# sensor_v21.net
KiCad netlist of a schematic drawn in EAGLE
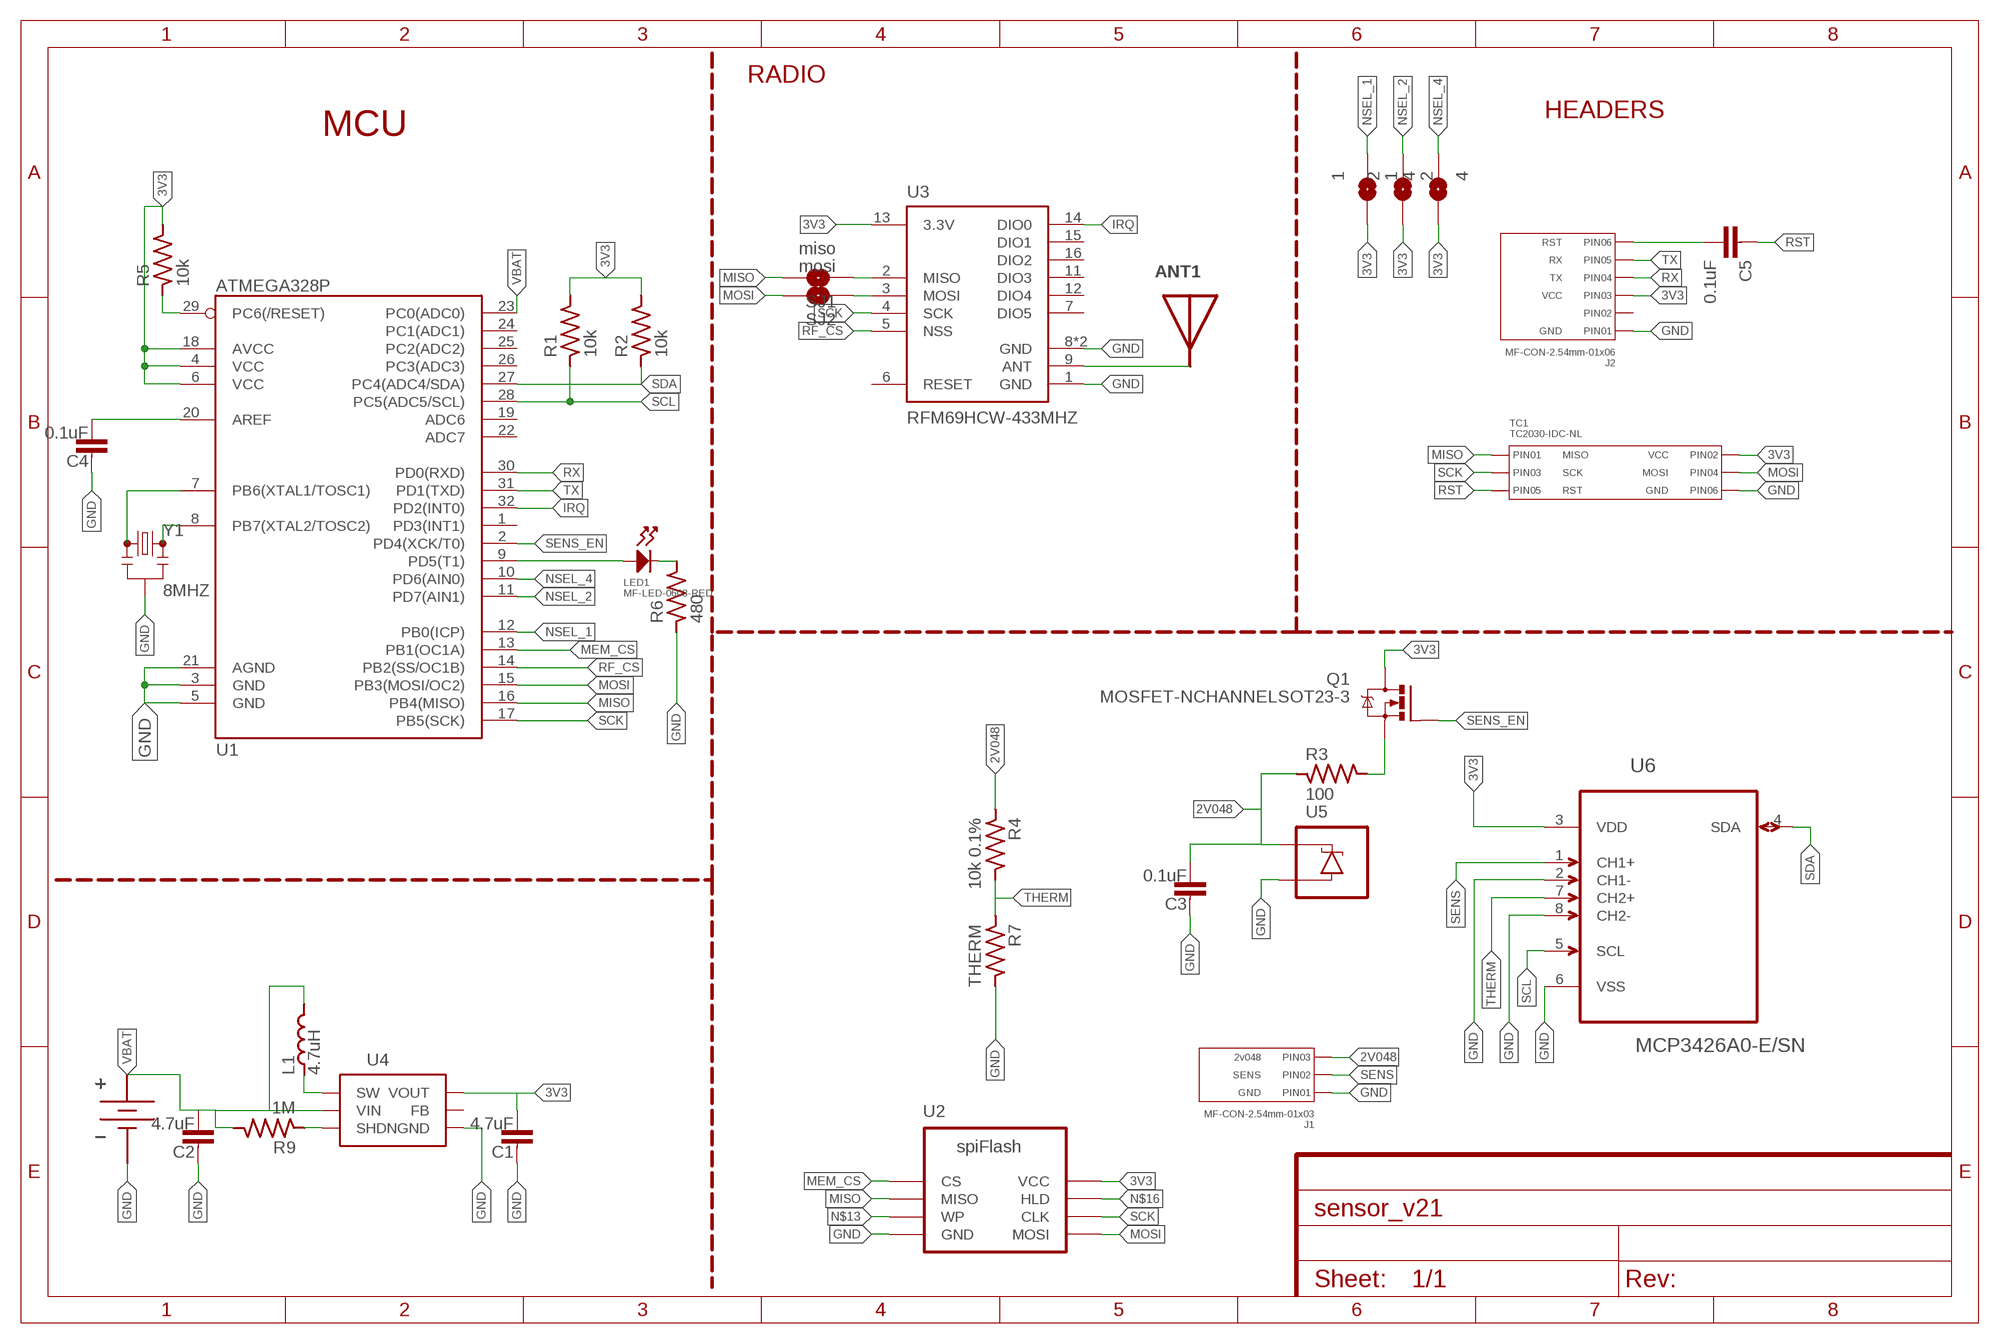
[diagram p0: schematic, sheet 1]

(export (version "E")
  (design (tool "Eeschema 10.0.6"))
  (components
    (comp (ref "1")
      (value "1")
      (footprint "eagle-import:SJ_2S-NOTRACE")
      (libsource (lib "eagle-import") (part "SOLDERJUMPERNC2"))
    )
    (comp (ref "2")
      (value "2")
      (footprint "eagle-import:SJ_2S-NOTRACE")
      (libsource (lib "eagle-import") (part "SOLDERJUMPERNC2"))
    )
    (comp (ref "4")
      (value "4")
      (footprint "eagle-import:SJ_2S-NOTRACE")
      (libsource (lib "eagle-import") (part "SOLDERJUMPERNC2"))
    )
    (comp (ref "ANT1")
      (value "ANTENNA-433_CHIP")
      (footprint "eagle-import:ANT_433_CHIP")
      (fields (field (name "PARTNO") "0433AT62A0020E"))
      (libsource (lib "eagle-import") (part "ANTENNA-433_CHIP"))
    )
    (comp (ref "C1")
      (value "4.7uF")
      (footprint "eagle-import:C0603-N")
      (libsource (lib "eagle-import") (part "CAPACITOR_NP0603-N"))
    )
    (comp (ref "C2")
      (value "4.7uF")
      (footprint "eagle-import:C0603-N")
      (libsource (lib "eagle-import") (part "CAPACITOR_NP0603-N"))
    )
    (comp (ref "C3")
      (value "0.1uF")
      (footprint "eagle-import:C0603-N")
      (libsource (lib "eagle-import") (part "CAPACITOR_NP0603-N"))
    )
    (comp (ref "C4")
      (value "0.1uF")
      (footprint "eagle-import:C0603-N")
      (libsource (lib "eagle-import") (part "CAPACITOR_NP0603-N"))
    )
    (comp (ref "C5")
      (value "0.1uF")
      (footprint "eagle-import:C0603-N")
      (libsource (lib "eagle-import") (part "CAPACITOR0603-N"))
    )
    (comp (ref "J1")
      (value "MF-CON-2.54mm-01x03")
      (footprint "eagle-import:PTH_2.54MM_01X03")
      (fields
        (field (name "HOUSEPART") "YES")
        (field (name "LABEL01") "GND")
        (field (name "LABEL02") "SENS")
        (field (name "LABEL03") "2v048")
        (field (name "PARTNO") "0022053031")
      )
      (libsource (lib "eagle-import") (part "CON_01X03_PTH_2.54MM"))
    )
    (comp (ref "J2")
      (value "MF-CON-2.54mm-01x06")
      (footprint "eagle-import:PTH_2.54MM_01X06")
      (fields
        (field (name "HOUSEPART") "YES")
        (field (name "LABEL01") "GND")
        (field (name "LABEL03") "VCC")
        (field (name "LABEL04") "TX")
        (field (name "LABEL05") "RX")
        (field (name "LABEL06") "RST")
      )
      (libsource (lib "eagle-import") (part "CON_01X06_PTH_2.54MM"))
    )
    (comp (ref "L1")
      (value "4.7uH")
      (footprint "eagle-import:L3030")
      (libsource (lib "eagle-import") (part "INDUCTOR3030"))
    )
    (comp (ref "LED1")
      (value "MF-LED-0603-RED")
      (footprint "eagle-import:LED0603")
      (fields (field (name "HOUSEPART") "YES"))
      (libsource (lib "eagle-import") (part "LED_SINGLE-0603-RED"))
    )
    (comp (ref "Q1")
      (value "MOSFET-NCHANNELSOT23-3")
      (footprint "eagle-import:SOT23-3")
      (libsource (lib "eagle-import") (part "MOSFET-NCHANNELSOT23-3"))
    )
    (comp (ref "R1")
      (value "10k")
      (footprint "eagle-import:R0603-N")
      (libsource (lib "eagle-import") (part "RESISTOR0603-N"))
    )
    (comp (ref "R2")
      (value "10k")
      (footprint "eagle-import:R0603-N")
      (libsource (lib "eagle-import") (part "RESISTOR0603-N"))
    )
    (comp (ref "R3")
      (value "100")
      (footprint "eagle-import:R0603-N")
      (libsource (lib "eagle-import") (part "RESISTOR0603-N"))
    )
    (comp (ref "R4")
      (value "10k 0.1%")
      (footprint "eagle-import:R0603-N")
      (fields (field (name "PARTNO") "0.1% !!"))
      (libsource (lib "eagle-import") (part "RESISTOR0603-N"))
    )
    (comp (ref "R5")
      (value "10k")
      (footprint "eagle-import:R0603-N")
      (libsource (lib "eagle-import") (part "RESISTOR0603-N"))
    )
    (comp (ref "R6")
      (value "480")
      (footprint "eagle-import:R0603-N")
      (libsource (lib "eagle-import") (part "RESISTOR0603-N"))
    )
    (comp (ref "R7")
      (value "THERM")
      (footprint "eagle-import:R0603-N")
      (fields (field (name "PARTNO") "FIND PART!!"))
      (libsource (lib "eagle-import") (part "RESISTOR0603-N"))
    )
    (comp (ref "R9")
      (value "1M")
      (footprint "eagle-import:R0603-N")
      (libsource (lib "eagle-import") (part "RESISTOR0603-N"))
    )
    (comp (ref "SJ1")
      (value "miso")
      (footprint "eagle-import:SJ_2S-NOTRACE")
      (libsource (lib "eagle-import") (part "SOLDERJUMPERNC2"))
    )
    (comp (ref "SJ2")
      (value "mosi")
      (footprint "eagle-import:SJ_2S-NOTRACE")
      (libsource (lib "eagle-import") (part "SOLDERJUMPERNC2"))
    )
    (comp (ref "TC1")
      (value "TC2030-IDC-NL")
      (footprint "eagle-import:TC2030-IDC-NL")
      (fields (field (name "HOUSEPART") "NO") (field (name "PARTNO") "NA"))
      (libsource (lib "eagle-import") (part "CON_02X03_TC2030-IDC-NL_AVRISP"))
    )
    (comp (ref "U$1")
      (value "KEYSTONEAAHOLDER_2CELL")
      (footprint "eagle-import:KEYSTONEAAHOLDER_2CELL")
      (libsource (lib "eagle-import") (part "KEYSTONEAAHOLDER_2CELL"))
    )
    (comp (ref "U1")
      (value "ATMEGA328P")
      (footprint "eagle-import:TQFP32")
      (libsource (lib "eagle-import") (part "ATMEGA328P_SMD-AU"))
    )
    (comp (ref "U2")
      (value "WINBOND_FLASH_4MBIT-SOIC")
      (footprint "eagle-import:SOIC8")
      (libsource (lib "eagle-import") (part "WINBOND_FLASH_4MBIT-SOIC"))
    )
    (comp (ref "U3")
      (value "RFM69HCW-433MHZ")
      (footprint "eagle-import:RFM69HCW-XXXS2")
      (fields (field (name "PARTNO") "COM-13910"))
      (libsource (lib "eagle-import") (part "RFM69HCW-433MHZ"))
    )
    (comp (ref "U4")
      (value "AAT1217-SOT23-6")
      (footprint "eagle-import:SOT23-6")
      (fields (field (name "PARTNO") "AAT1217ICA-3.3-T1"))
      (libsource (lib "eagle-import") (part "AAT1217-SOT23-6"))
    )
    (comp (ref "U5")
      (value "LM4040-SOT-23-3")
      (footprint "eagle-import:SOT23-3")
      (fields (field (name "PARTNO") "LM4040AIM3-2.0/NOPB "))
      (libsource (lib "eagle-import") (part "LM4040-SOT-23-3"))
    )
    (comp (ref "U6")
      (value "MCP3426A0-E/SN")
      (footprint "eagle-import:SOIC127P600X175-8N")
      (libsource (lib "eagle-import") (part "MCP3426A0-E/SN"))
    )
    (comp (ref "Y1")
      (value "8MHZ")
      (footprint "eagle-import:RESONATOR-SMD")
      (fields (field (name "PARTNO") "CSTCE8M00G55-R0"))
      (libsource (lib "eagle-import") (part "RESONATOR8MHZ"))
    )
  )
  (nets
    (net (code "1") (name "2V048") (class "Default")
      (node (ref "C3") (pin "2") (pinfunction "2_2") (pintype "passive"))
      (node (ref "J1") (pin "P$3") (pinfunction "PIN3_P$3") (pintype "bidirectional"))
      (node (ref "R3") (pin "1") (pinfunction "P$1_1") (pintype "passive"))
      (node (ref "R4") (pin "1") (pinfunction "P$1_1") (pintype "passive"))
      (node (ref "U5") (pin "1") (pinfunction "C_1") (pintype "bidirectional"))
    )
    (net (code "2") (name "3V3") (class "Default")
      (node (ref "1") (pin "2") (pinfunction "2_2") (pintype "passive"))
      (node (ref "2") (pin "2") (pinfunction "2_2") (pintype "passive"))
      (node (ref "4") (pin "2") (pinfunction "2_2") (pintype "passive"))
      (node (ref "C1") (pin "2") (pinfunction "2_2") (pintype "passive"))
      (node (ref "J2") (pin "P$3") (pinfunction "PIN3_P$3") (pintype "bidirectional"))
      (node (ref "Q1") (pin "3") (pinfunction "D_3") (pintype "passive"))
      (node (ref "R1") (pin "2") (pinfunction "P$2_2") (pintype "passive"))
      (node (ref "R2") (pin "2") (pinfunction "P$2_2") (pintype "passive"))
      (node (ref "R5") (pin "2") (pinfunction "P$2_2") (pintype "passive"))
      (node (ref "TC1") (pin "P$2") (pinfunction "PIN2_P$2") (pintype "bidirectional"))
      (node (ref "U1") (pin "18") (pinfunction "AVCC_18") (pintype "bidirectional"))
      (node (ref "U1") (pin "4") (pinfunction "VCC_4") (pintype "bidirectional"))
      (node (ref "U1") (pin "6") (pinfunction "VCC_6") (pintype "bidirectional"))
      (node (ref "U2") (pin "8") (pinfunction "VCC_8") (pintype "bidirectional"))
      (node (ref "U3") (pin "13") (pinfunction "3.3V_13") (pintype "power_in"))
      (node (ref "U4") (pin "5") (pinfunction "VOUT_5") (pintype "bidirectional"))
      (node (ref "U6") (pin "3") (pinfunction "VDD_3") (pintype "power_in"))
    )
    (net (code "3") (name "GND") (class "Default")
      (node (ref "C1") (pin "1") (pinfunction "1_1") (pintype "passive"))
      (node (ref "C2") (pin "1") (pinfunction "1_1") (pintype "passive"))
      (node (ref "C3") (pin "1") (pinfunction "1_1") (pintype "passive"))
      (node (ref "C4") (pin "1") (pinfunction "1_1") (pintype "passive"))
      (node (ref "J1") (pin "P$1") (pinfunction "PIN1_P$1") (pintype "bidirectional"))
      (node (ref "J2") (pin "P$1") (pinfunction "PIN1_P$1") (pintype "bidirectional"))
      (node (ref "R6") (pin "1") (pinfunction "P$1_1") (pintype "passive"))
      (node (ref "R7") (pin "2") (pinfunction "P$2_2") (pintype "passive"))
      (node (ref "TC1") (pin "P$6") (pinfunction "PIN6_P$6") (pintype "bidirectional"))
      (node (ref "U$1") (pin "P$2") (pinfunction "GND_P$2") (pintype "bidirectional"))
      (node (ref "U1") (pin "21") (pinfunction "AGND_21") (pintype "bidirectional"))
      (node (ref "U1") (pin "3") (pinfunction "GND_3") (pintype "bidirectional"))
      (node (ref "U1") (pin "5") (pinfunction "GND_5") (pintype "bidirectional"))
      (node (ref "U2") (pin "4") (pinfunction "GND_4") (pintype "bidirectional"))
      (node (ref "U3") (pin "1") (pinfunction "GND_1") (pintype "power_in"))
      (node (ref "U3") (pin "10") (pinfunction "GND_10") (pintype "power_in"))
      (node (ref "U3") (pin "8") (pinfunction "GND_8") (pintype "power_in"))
      (node (ref "U4") (pin "2") (pinfunction "GND_2") (pintype "bidirectional"))
      (node (ref "U5") (pin "2") (pinfunction "A_2") (pintype "bidirectional"))
      (node (ref "U6") (pin "2") (pinfunction "CH1-_2") (pintype "input"))
      (node (ref "U6") (pin "6") (pinfunction "VSS_6") (pintype "power_in"))
      (node (ref "U6") (pin "8") (pinfunction "CH2-_8") (pintype "input"))
      (node (ref "Y1") (pin "2") (pinfunction "2_2") (pintype "passive"))
    )
    (net (code "4") (name "IRQ") (class "Default")
      (node (ref "U1") (pin "32") (pinfunction "PD2(INT0)_32") (pintype "bidirectional"))
      (node (ref "U3") (pin "14") (pinfunction "DIO0_14") (pintype "bidirectional"))
    )
    (net (code "5") (name "MEM_CS") (class "Default")
      (node (ref "U1") (pin "13") (pinfunction "PB1(OC1A)_13") (pintype "bidirectional"))
      (node (ref "U2") (pin "1") (pinfunction "CS_1") (pintype "bidirectional"))
    )
    (net (code "6") (name "MISO") (class "Default")
      (node (ref "SJ1") (pin "2") (pinfunction "2_2") (pintype "passive"))
      (node (ref "TC1") (pin "P$1") (pinfunction "PIN1_P$1") (pintype "bidirectional"))
      (node (ref "U1") (pin "16") (pinfunction "PB4(MISO)_16") (pintype "bidirectional"))
      (node (ref "U2") (pin "2") (pinfunction "MISO_2") (pintype "bidirectional"))
    )
    (net (code "7") (name "MOSI") (class "Default")
      (node (ref "SJ2") (pin "2") (pinfunction "2_2") (pintype "passive"))
      (node (ref "TC1") (pin "P$4") (pinfunction "PIN4_P$4") (pintype "bidirectional"))
      (node (ref "U1") (pin "15") (pinfunction "PB3(MOSI/OC2)_15") (pintype "bidirectional"))
      (node (ref "U2") (pin "5") (pinfunction "MOSI_5") (pintype "bidirectional"))
    )
    (net (code "8") (name "N$13") (class "Default")
      (node (ref "U2") (pin "3") (pinfunction "WP_3") (pintype "bidirectional"))
    )
    (net (code "9") (name "N$16") (class "Default")
      (node (ref "U2") (pin "7") (pinfunction "HLD_7") (pintype "bidirectional"))
    )
    (net (code "10") (name "NSEL_1") (class "Default")
      (node (ref "1") (pin "1") (pinfunction "1_1") (pintype "passive"))
      (node (ref "U1") (pin "12") (pinfunction "PB0(ICP)_12") (pintype "bidirectional"))
    )
    (net (code "11") (name "NSEL_2") (class "Default")
      (node (ref "2") (pin "1") (pinfunction "1_1") (pintype "passive"))
      (node (ref "U1") (pin "11") (pinfunction "PD7(AIN1)_11") (pintype "bidirectional"))
    )
    (net (code "12") (name "NSEL_4") (class "Default")
      (node (ref "4") (pin "1") (pinfunction "1_1") (pintype "passive"))
      (node (ref "U1") (pin "10") (pinfunction "PD6(AIN0)_10") (pintype "bidirectional"))
    )
    (net (code "13") (name "Net-(J2-PIN6)") (class "Default")
      (node (ref "C5") (pin "2") (pinfunction "2_2") (pintype "passive"))
      (node (ref "J2") (pin "P$6") (pinfunction "PIN6_P$6") (pintype "bidirectional"))
    )
    (net (code "14") (name "Net-(Q1-S)") (class "Default")
      (node (ref "Q1") (pin "2") (pinfunction "S_2") (pintype "passive"))
      (node (ref "R3") (pin "2") (pinfunction "P$2_2") (pintype "passive"))
    )
    (net (code "15") (name "Net-(R6-P$2)") (class "Default")
      (node (ref "LED1") (pin "CATHODE") (pinfunction "CATHODE_CATHODE") (pintype "power_in"))
      (node (ref "R6") (pin "2") (pinfunction "P$2_2") (pintype "passive"))
    )
    (net (code "16") (name "Net-(R9-P$1)") (class "Default")
      (node (ref "R9") (pin "1") (pinfunction "P$1_1") (pintype "passive"))
      (node (ref "U4") (pin "4") (pinfunction "SHDN_4") (pintype "bidirectional"))
    )
    (net (code "17") (name "Net-(U1-AREF)") (class "Default")
      (node (ref "C4") (pin "2") (pinfunction "2_2") (pintype "passive"))
      (node (ref "U1") (pin "20") (pinfunction "AREF_20") (pintype "bidirectional"))
    )
    (net (code "18") (name "Net-(U1-PB6(XTAL1{slash}TOSC1))") (class "Default")
      (node (ref "U1") (pin "7") (pinfunction "PB6(XTAL1/TOSC1)_7") (pintype "bidirectional"))
      (node (ref "Y1") (pin "1") (pinfunction "1_1") (pintype "passive"))
    )
    (net (code "19") (name "Net-(U1-PB7(XTAL2{slash}TOSC2))") (class "Default")
      (node (ref "U1") (pin "8") (pinfunction "PB7(XTAL2/TOSC2)_8") (pintype "bidirectional"))
      (node (ref "Y1") (pin "3") (pinfunction "3_3") (pintype "passive"))
    )
    (net (code "20") (name "Net-(U1-PD5(T1))") (class "Default")
      (node (ref "LED1") (pin "ANODE") (pinfunction "ANODE_ANODE") (pintype "power_in"))
      (node (ref "U1") (pin "9") (pinfunction "PD5(T1)_9") (pintype "bidirectional"))
    )
    (net (code "21") (name "Net-(U3-ANT)") (class "Default")
      (node (ref "ANT1") (pin "1") (pinfunction "1_1") (pintype "bidirectional"))
      (node (ref "U3") (pin "9") (pinfunction "ANT_9") (pintype "passive"))
    )
    (net (code "22") (name "Net-(U3-MISO)") (class "Default")
      (node (ref "SJ1") (pin "1") (pinfunction "1_1") (pintype "passive"))
      (node (ref "U3") (pin "2") (pinfunction "MISO_2") (pintype "bidirectional"))
    )
    (net (code "23") (name "Net-(U3-MOSI)") (class "Default")
      (node (ref "SJ2") (pin "1") (pinfunction "1_1") (pintype "passive"))
      (node (ref "U3") (pin "3") (pinfunction "MOSI_3") (pintype "input"))
    )
    (net (code "24") (name "Net-(U4-SW)") (class "Default")
      (node (ref "L1") (pin "P$1") (pinfunction "P$1_P$1") (pintype "passive"))
      (node (ref "U4") (pin "1") (pinfunction "SW_1") (pintype "bidirectional"))
    )
    (net (code "25") (name "RF_CS") (class "Default")
      (node (ref "U1") (pin "14") (pinfunction "PB2(SS/OC1B)_14") (pintype "bidirectional"))
      (node (ref "U3") (pin "5") (pinfunction "NSS_5") (pintype "input"))
    )
    (net (code "26") (name "RST") (class "Default")
      (node (ref "C5") (pin "1") (pinfunction "1_1") (pintype "passive"))
      (node (ref "R5") (pin "1") (pinfunction "P$1_1") (pintype "passive"))
      (node (ref "TC1") (pin "P$5") (pinfunction "PIN5_P$5") (pintype "bidirectional"))
      (node (ref "U1") (pin "29") (pinfunction "PC6(/RESET)_29") (pintype "bidirectional"))
    )
    (net (code "27") (name "RX") (class "Default")
      (node (ref "J2") (pin "P$4") (pinfunction "PIN4_P$4") (pintype "bidirectional"))
      (node (ref "U1") (pin "30") (pinfunction "PD0(RXD)_30") (pintype "bidirectional"))
    )
    (net (code "28") (name "SCK") (class "Default")
      (node (ref "TC1") (pin "P$3") (pinfunction "PIN3_P$3") (pintype "bidirectional"))
      (node (ref "U1") (pin "17") (pinfunction "PB5(SCK)_17") (pintype "bidirectional"))
      (node (ref "U2") (pin "6") (pinfunction "CLK_6") (pintype "bidirectional"))
      (node (ref "U3") (pin "4") (pinfunction "SCK_4") (pintype "input"))
    )
    (net (code "29") (name "SCL") (class "Default")
      (node (ref "R1") (pin "1") (pinfunction "P$1_1") (pintype "passive"))
      (node (ref "U1") (pin "28") (pinfunction "PC5(ADC5/SCL)_28") (pintype "bidirectional"))
      (node (ref "U6") (pin "5") (pinfunction "SCL_5") (pintype "input"))
    )
    (net (code "30") (name "SDA") (class "Default")
      (node (ref "R2") (pin "1") (pinfunction "P$1_1") (pintype "passive"))
      (node (ref "U1") (pin "27") (pinfunction "PC4(ADC4/SDA)_27") (pintype "bidirectional"))
      (node (ref "U6") (pin "4") (pinfunction "SDA_4") (pintype "bidirectional"))
    )
    (net (code "31") (name "SENS") (class "Default")
      (node (ref "J1") (pin "P$2") (pinfunction "PIN2_P$2") (pintype "bidirectional"))
      (node (ref "U6") (pin "1") (pinfunction "CH1+_1") (pintype "input"))
    )
    (net (code "32") (name "SENS_EN") (class "Default")
      (node (ref "Q1") (pin "1") (pinfunction "G_1") (pintype "passive"))
      (node (ref "U1") (pin "2") (pinfunction "PD4(XCK/T0)_2") (pintype "bidirectional"))
    )
    (net (code "33") (name "THERM") (class "Default")
      (node (ref "R4") (pin "2") (pinfunction "P$2_2") (pintype "passive"))
      (node (ref "R7") (pin "1") (pinfunction "P$1_1") (pintype "passive"))
      (node (ref "U6") (pin "7") (pinfunction "CH2+_7") (pintype "input"))
    )
    (net (code "34") (name "TX") (class "Default")
      (node (ref "J2") (pin "P$5") (pinfunction "PIN5_P$5") (pintype "bidirectional"))
      (node (ref "U1") (pin "31") (pinfunction "PD1(TXD)_31") (pintype "bidirectional"))
    )
    (net (code "35") (name "VBAT") (class "Default")
      (node (ref "C2") (pin "2") (pinfunction "2_2") (pintype "passive"))
      (node (ref "L1") (pin "P$2") (pinfunction "P$2_P$2") (pintype "passive"))
      (node (ref "R9") (pin "2") (pinfunction "P$2_2") (pintype "passive"))
      (node (ref "U$1") (pin "P$1") (pinfunction "VBAT_P$1") (pintype "bidirectional"))
      (node (ref "U1") (pin "23") (pinfunction "PC0(ADC0)_23") (pintype "bidirectional"))
      (node (ref "U4") (pin "6") (pinfunction "VIN_6") (pintype "bidirectional"))
    )
    (net (code "36") (name "unconnected-(J2-PIN2-PadP$2)") (class "Default")
      (node (ref "J2") (pin "P$2") (pinfunction "PIN2_P$2") (pintype "bidirectional"))
    )
    (net (code "37") (name "unconnected-(U1-ADC6-Pad19)") (class "Default")
      (node (ref "U1") (pin "19") (pinfunction "ADC6_19") (pintype "bidirectional"))
    )
    (net (code "38") (name "unconnected-(U1-ADC7-Pad22)") (class "Default")
      (node (ref "U1") (pin "22") (pinfunction "ADC7_22") (pintype "bidirectional"))
    )
    (net (code "39") (name "unconnected-(U1-PC1(ADC1)-Pad24)") (class "Default")
      (node (ref "U1") (pin "24") (pinfunction "PC1(ADC1)_24") (pintype "bidirectional"))
    )
    (net (code "40") (name "unconnected-(U1-PC2(ADC2)-Pad25)") (class "Default")
      (node (ref "U1") (pin "25") (pinfunction "PC2(ADC2)_25") (pintype "bidirectional"))
    )
    (net (code "41") (name "unconnected-(U1-PC3(ADC3)-Pad26)") (class "Default")
      (node (ref "U1") (pin "26") (pinfunction "PC3(ADC3)_26") (pintype "bidirectional"))
    )
    (net (code "42") (name "unconnected-(U1-PD3(INT1)-Pad1)") (class "Default")
      (node (ref "U1") (pin "1") (pinfunction "PD3(INT1)_1") (pintype "bidirectional"))
    )
    (net (code "43") (name "unconnected-(U3-DIO1-Pad15)") (class "Default")
      (node (ref "U3") (pin "15") (pinfunction "DIO1_15") (pintype "bidirectional"))
    )
    (net (code "44") (name "unconnected-(U3-DIO2-Pad16)") (class "Default")
      (node (ref "U3") (pin "16") (pinfunction "DIO2_16") (pintype "bidirectional"))
    )
    (net (code "45") (name "unconnected-(U3-DIO3-Pad11)") (class "Default")
      (node (ref "U3") (pin "11") (pinfunction "DIO3_11") (pintype "bidirectional"))
    )
    (net (code "46") (name "unconnected-(U3-DIO4-Pad12)") (class "Default")
      (node (ref "U3") (pin "12") (pinfunction "DIO4_12") (pintype "bidirectional"))
    )
    (net (code "47") (name "unconnected-(U3-DIO5-Pad7)") (class "Default")
      (node (ref "U3") (pin "7") (pinfunction "DIO5_7") (pintype "bidirectional"))
    )
    (net (code "48") (name "unconnected-(U3-RESET-Pad6)") (class "Default")
      (node (ref "U3") (pin "6") (pinfunction "RESET_6") (pintype "input"))
    )
    (net (code "49") (name "unconnected-(U4-FB-Pad3)") (class "Default")
      (node (ref "U4") (pin "3") (pinfunction "FB_3") (pintype "bidirectional"))
    )
  )
)
